# Power.net
KiCad netlist of a schematic drawn in Altium Designer
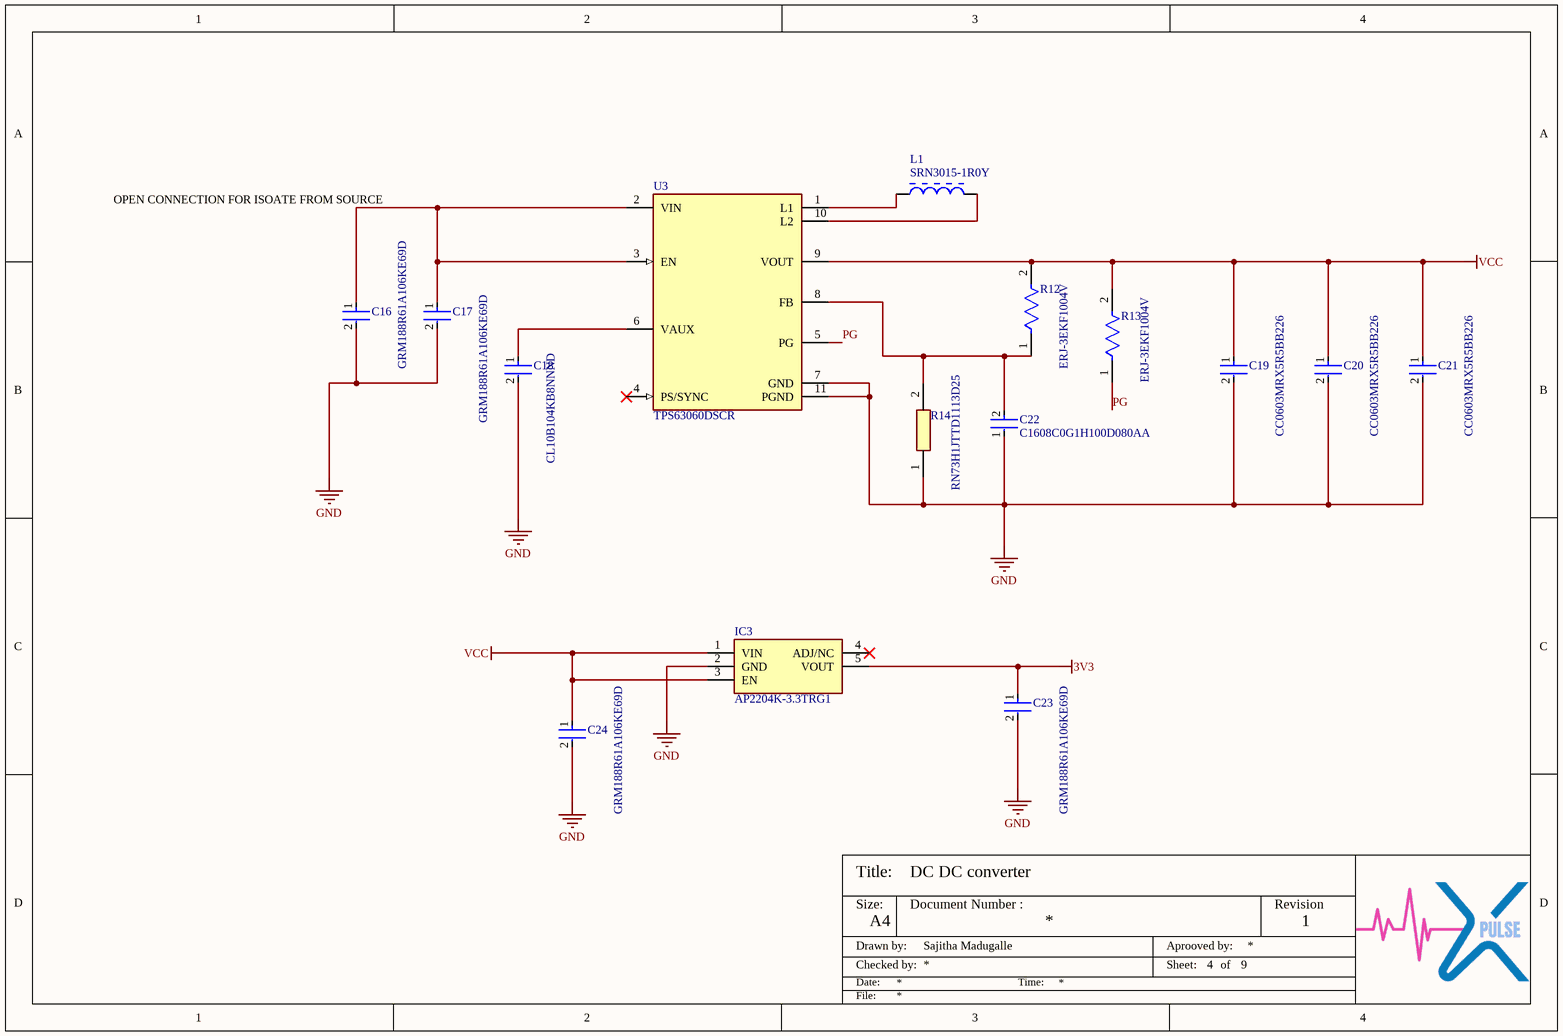
[diagram p0: Power.SchDoc]

(export (version "E")
  (design (tool "Eeschema 10.0.6"))
  (components
    (comp (ref "C16")
      (value "GRM188R61A106KE69D")
      (footprint "FP-GRM18-0_15-MFG")
      (description "CAP CER 10UF 10V X5R 0603")
      (fields
        (field (name "OCTOPART") "https://octopart.com/grm188r61a106ke69d-murata-22851381")
        (field (name "MANUFACTURER") "Murata")
      )
      (libsource (lib "Altium Content Vault") (part "11868f565c42a9108669ba33697ecf6"))
    )
    (comp (ref "C17")
      (value "GRM188R61A106KE69D")
      (footprint "FP-GRM18-0_15-MFG")
      (description "CAP CER 10UF 10V X5R 0603")
      (fields
        (field (name "OCTOPART") "https://octopart.com/grm188r61a106ke69d-murata-22851381")
        (field (name "MANUFACTURER") "Murata")
      )
      (libsource (lib "Altium Content Vault") (part "11868f565c42a9108669ba33697ecf6"))
    )
    (comp (ref "C18")
      (value "CL10B104KB8NNND")
      (footprint "FP-CL10-IPC_A")
      (description "Cap Ceramic 100nF 50V X7R ±10% Pad SMD 0603 +125°C T/R")
      (fields (field (name "VOLTAGE") "50V") (field (name "TOLERANCE") "10%"))
      (libsource (lib "Altium Content Vault") (part "b4654b650e69147ec39a6b967a45e02"))
    )
    (comp (ref "C19")
      (value "CC0603MRX5R5BB226")
      (footprint "FP-CC0603-DC-MFG")
      (description "CAP CER 22UF 6.3V X5R 0603")
      (fields (field (name "TOLERANCE") "20%"))
      (libsource (lib "Altium Content Vault") (part "b4654b650e69147ec39a6b967a45e02"))
    )
    (comp (ref "C20")
      (value "CC0603MRX5R5BB226")
      (footprint "FP-CC0603-DC-MFG")
      (description "CAP CER 22UF 6.3V X5R 0603")
      (fields (field (name "TOLERANCE") "20%"))
      (libsource (lib "Altium Content Vault") (part "b4654b650e69147ec39a6b967a45e02"))
    )
    (comp (ref "C21")
      (value "CC0603MRX5R5BB226")
      (footprint "FP-CC0603-DC-MFG")
      (description "CAP CER 22UF 6.3V X5R 0603")
      (fields (field (name "TOLERANCE") "20%"))
      (libsource (lib "Altium Content Vault") (part "b4654b650e69147ec39a6b967a45e02"))
    )
    (comp (ref "C22")
      (value "C1608C0G1H100D080AA")
      (footprint "FP-C1608-080-0_1-IPC_C")
      (description "Multilayer Ceramic Capacitors 10pF ±0.5pF 50V C0G SMD 0603")
      (fields (field (name "VOLTAGE") "50V") (field (name "TOLERANCE") "5%"))
      (libsource (lib "Altium Content Vault") (part "236180d848d6139a670b325ea6854c9"))
    )
    (comp (ref "C23")
      (value "GRM188R61A106KE69D")
      (footprint "FP-GRM18-0_15-MFG")
      (description "CAP CER 10UF 10V X5R 0603")
      (fields
        (field (name "OCTOPART") "https://octopart.com/grm188r61a106ke69d-murata-22851381")
        (field (name "MANUFACTURER") "Murata")
      )
      (libsource (lib "Altium Content Vault") (part "11868f565c42a9108669ba33697ecf6"))
    )
    (comp (ref "C24")
      (value "GRM188R61A106KE69D")
      (footprint "FP-GRM18-0_15-MFG")
      (description "CAP CER 10UF 10V X5R 0603")
      (fields
        (field (name "OCTOPART") "https://octopart.com/grm188r61a106ke69d-murata-22851381")
        (field (name "MANUFACTURER") "Murata")
      )
      (libsource (lib "Altium Content Vault") (part "11868f565c42a9108669ba33697ecf6"))
    )
    (comp (ref "IC3")
      (value "AP2204K-3.3TRG1")
      (footprint "SamacSys:SOT95P282X145-5N")
      (description "Integrated Circuit")
      (fields (field (name "MOUSER PART NUMBER") "621-AP2204K-3.3TRG1"))
      (libsource (lib "*") (part "AP2204K-3.3TRG1"))
    )
    (comp (ref "L1")
      (value "SRN3015-1R0Y")
      (footprint "BOUR-SRN3015-2_V")
      (fields (field (name "MANUFACTURER") "Bourns"))
      (libsource (lib "Altium Content Vault") (part "BOUR-IND-2A"))
    )
    (comp (ref "R12")
      (value "ERJ-3EKF1004V")
      (footprint "FP-ERJ3EK-IPC_C")
      (description "RES SMD 1M OHM 1% 1/10W 0603")
      (fields (field (name "TOLERANCE") "1%"))
      (libsource (lib "Altium Content Vault") (part "1029c3af85768c4190bb7ad29bc67b5"))
    )
    (comp (ref "R13")
      (value "ERJ-3EKF1004V")
      (footprint "FP-ERJ3EK-IPC_C")
      (description "RES SMD 1M OHM 1% 1/10W 0603")
      (fields (field (name "TOLERANCE") "1%"))
      (libsource (lib "Altium Content Vault") (part "1029c3af85768c4190bb7ad29bc67b5"))
    )
    (comp (ref "R14")
      (value "RN73H1JTTD1113D25")
      (footprint "SamacSys:RESC1608X55N")
      (description "Resistor")
      (fields (field (name "MOUSER PART NUMBER") "660-RN73H1JTD1113D25"))
      (libsource (lib "*") (part "RN73H1JTTD1113D25"))
    )
    (comp (ref "U3")
      (value "TPS63060DSCR")
      (footprint "FP-DSC0010G-MFG")
      (description "IC REG BCK BST ADJ 2A 10WSON")
      (fields
        (field (name "OCTOPART") "https://octopart.com/tps63060dscr-texas+instruments-21396306")
        (field (name "MANUFACTURER") "Texas Instruments")
      )
      (libsource (lib "Altium Content Vault") (part "685ee7cb3382eb91975488bbdb76012"))
    )
  )
  (nets
    (net (code "1") (name "/PG") (class "Default")
      (node (ref "R13") (pin "1") (pinfunction "1_1") (pintype "passive"))
      (node (ref "U3") (pin "5") (pinfunction "PG_5") (pintype "open_collector"))
    )
    (net (code "2") (name "3V3") (class "Default")
      (node (ref "C23") (pin "1") (pinfunction "1_1") (pintype "passive"))
      (node (ref "IC3") (pin "5") (pinfunction "VOUT_5") (pintype "passive"))
    )
    (net (code "3") (name "GND") (class "Default")
      (node (ref "C16") (pin "2") (pinfunction "2_2") (pintype "passive"))
      (node (ref "C17") (pin "2") (pinfunction "2_2") (pintype "passive"))
      (node (ref "C18") (pin "2") (pinfunction "2_2") (pintype "passive"))
      (node (ref "C19") (pin "2") (pinfunction "2_2") (pintype "passive"))
      (node (ref "C20") (pin "2") (pinfunction "2_2") (pintype "passive"))
      (node (ref "C21") (pin "2") (pinfunction "2_2") (pintype "passive"))
      (node (ref "C22") (pin "1") (pinfunction "1_1") (pintype "passive"))
      (node (ref "C23") (pin "2") (pinfunction "2_2") (pintype "passive"))
      (node (ref "C24") (pin "2") (pinfunction "2_2") (pintype "passive"))
      (node (ref "IC3") (pin "2") (pinfunction "GND_2") (pintype "passive"))
      (node (ref "R14") (pin "1") (pinfunction "1_1") (pintype "passive"))
      (node (ref "U3") (pin "11") (pinfunction "PGND_11") (pintype "power_in"))
      (node (ref "U3") (pin "7") (pinfunction "GND_7") (pintype "power_in"))
    )
    (net (code "4") (name "Net-(U3-EN)") (class "Default")
      (node (ref "C16") (pin "1") (pinfunction "1_1") (pintype "passive"))
      (node (ref "C17") (pin "1") (pinfunction "1_1") (pintype "passive"))
      (node (ref "U3") (pin "2") (pinfunction "VIN_2") (pintype "power_in"))
      (node (ref "U3") (pin "3") (pinfunction "EN_3") (pintype "input"))
    )
    (net (code "5") (name "Net-(U3-FB)") (class "Default")
      (node (ref "C22") (pin "2") (pinfunction "2_2") (pintype "passive"))
      (node (ref "R12") (pin "1") (pinfunction "1_1") (pintype "passive"))
      (node (ref "R14") (pin "2") (pinfunction "2_2") (pintype "passive"))
      (node (ref "U3") (pin "8") (pinfunction "FB_8") (pintype "passive"))
    )
    (net (code "6") (name "Net-(U3-L1)") (class "Default")
      (node (ref "L1") (pin "1") (pinfunction "1_1") (pintype "passive"))
      (node (ref "U3") (pin "1") (pinfunction "L1_1") (pintype "passive"))
    )
    (net (code "7") (name "Net-(U3-L2)") (class "Default")
      (node (ref "L1") (pin "2") (pinfunction "2_2") (pintype "passive"))
      (node (ref "U3") (pin "10") (pinfunction "L2_10") (pintype "passive"))
    )
    (net (code "8") (name "Net-(U3-VAUX)") (class "Default")
      (node (ref "C18") (pin "1") (pinfunction "1_1") (pintype "passive"))
      (node (ref "U3") (pin "6") (pinfunction "VAUX_6") (pintype "passive"))
    )
    (net (code "9") (name "VCC") (class "Default")
      (node (ref "C19") (pin "1") (pinfunction "1_1") (pintype "passive"))
      (node (ref "C20") (pin "1") (pinfunction "1_1") (pintype "passive"))
      (node (ref "C21") (pin "1") (pinfunction "1_1") (pintype "passive"))
      (node (ref "C24") (pin "1") (pinfunction "1_1") (pintype "passive"))
      (node (ref "IC3") (pin "1") (pinfunction "VIN_1") (pintype "passive"))
      (node (ref "IC3") (pin "3") (pinfunction "EN_3") (pintype "passive"))
      (node (ref "R12") (pin "2") (pinfunction "2_2") (pintype "passive"))
      (node (ref "R13") (pin "2") (pinfunction "2_2") (pintype "passive"))
      (node (ref "U3") (pin "9") (pinfunction "VOUT_9") (pintype "power_in"))
    )
    (net (code "10") (name "unconnected-(IC3-ADJ{slash}NC-Pad4)") (class "Default")
      (node (ref "IC3") (pin "4") (pinfunction "ADJ/NC_4") (pintype "passive+no_connect"))
    )
    (net (code "11") (name "unconnected-(U3-PS{slash}SYNC-Pad4)") (class "Default")
      (node (ref "U3") (pin "4") (pinfunction "PS/SYNC_4") (pintype "input+no_connect"))
    )
  )
)
